# Main.net
KiCad netlist of a schematic drawn in Altium Designer
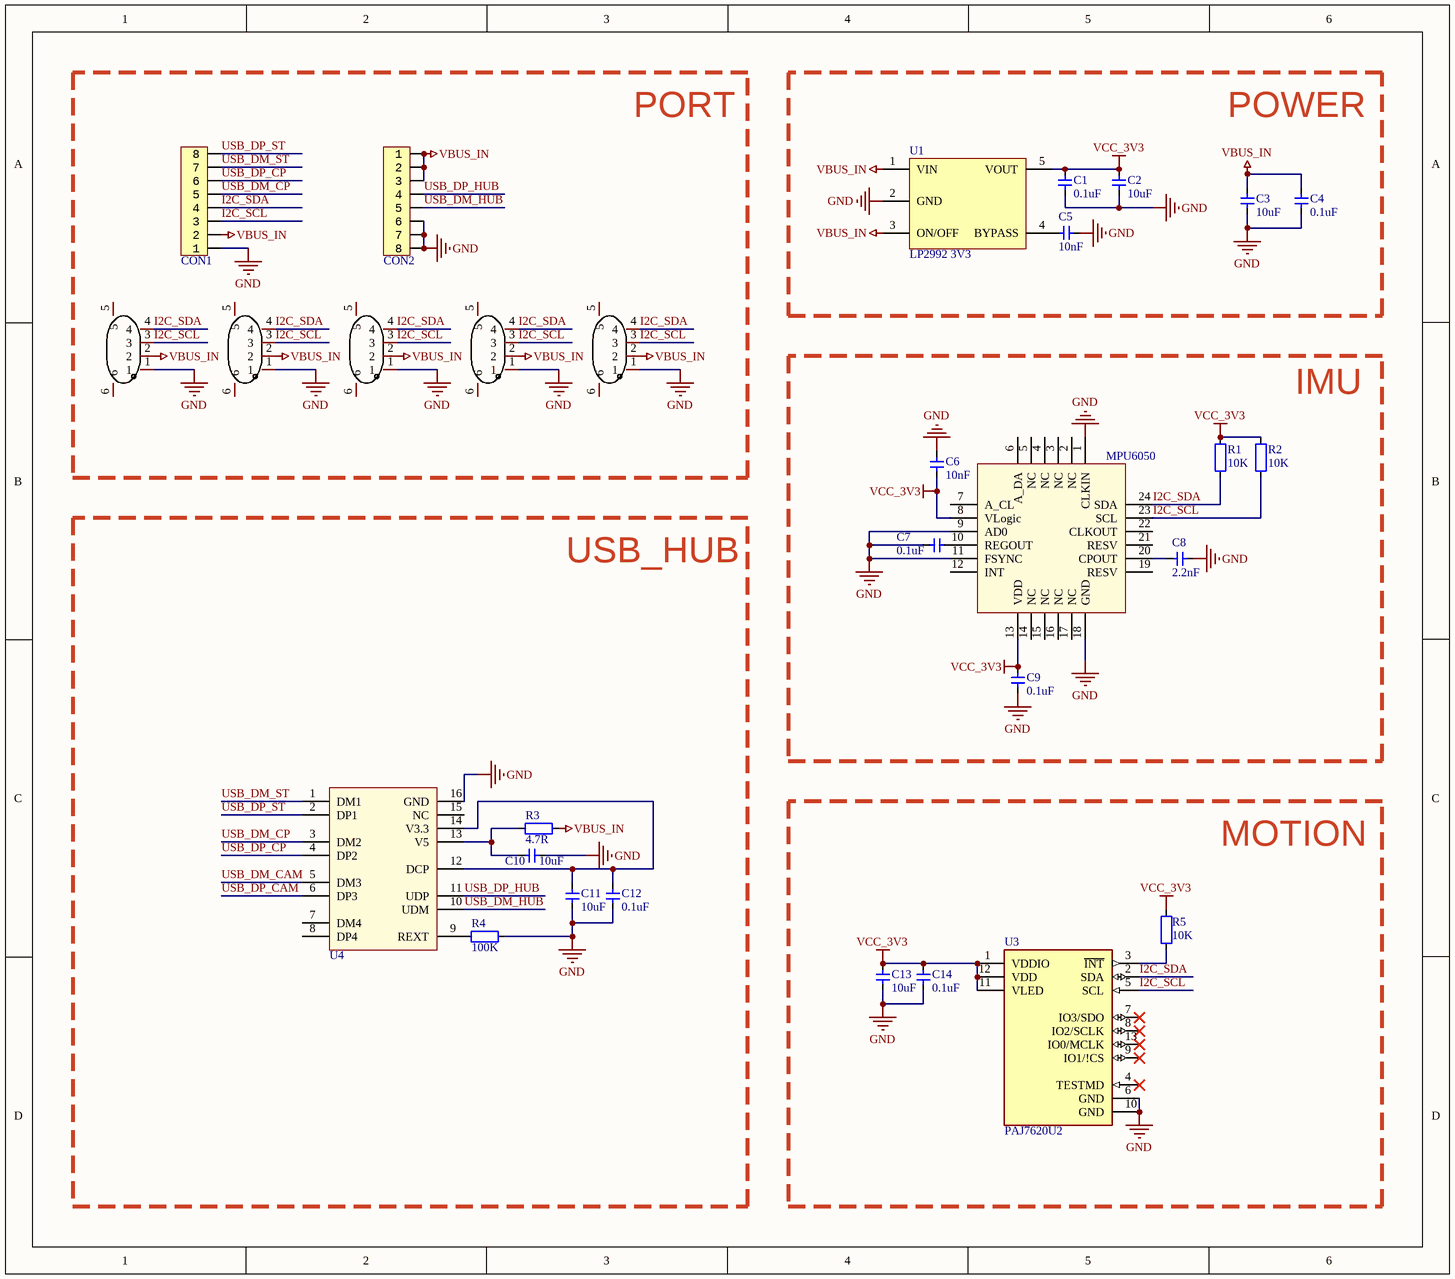
[diagram p0: Main.SchDoc]

(export (version "E")
  (design (tool "Eeschema 10.0.6"))
  (components
    (comp (ref "C1")
      (value "0.1uF")
      (footprint "CAP_0402")
      (description "Capacitor")
      (libsource (lib "MyPcbLib") (part "电容-0402"))
    )
    (comp (ref "C2")
      (value "10uF")
      (footprint "CAP_0402")
      (description "Capacitor")
      (libsource (lib "MyPcbLib") (part "电容-0402"))
    )
    (comp (ref "C3")
      (value "10uF")
      (footprint "CAP_0402")
      (description "Capacitor")
      (libsource (lib "MyPcbLib") (part "电容-0402"))
    )
    (comp (ref "C4")
      (value "0.1uF")
      (footprint "CAP_0402")
      (description "Capacitor")
      (libsource (lib "MyPcbLib") (part "电容-0402"))
    )
    (comp (ref "C5")
      (value "10nF")
      (footprint "CAP_0402")
      (description "Capacitor")
      (libsource (lib "MyPcbLib") (part "电容-0402"))
    )
    (comp (ref "C6")
      (value "10nF")
      (footprint "CAP_0402")
      (description "Capacitor")
      (libsource (lib "MyPcbLib") (part "电容-0402"))
    )
    (comp (ref "C7")
      (value "0.1uF")
      (footprint "CAP_0402")
      (description "Capacitor")
      (libsource (lib "MyPcbLib") (part "电容-0402"))
    )
    (comp (ref "C8")
      (value "2.2nF")
      (footprint "CAP_0402")
      (description "Capacitor")
      (libsource (lib "MyPcbLib") (part "电容-0402"))
    )
    (comp (ref "C9")
      (value "0.1uF")
      (footprint "CAP_0402")
      (description "Capacitor")
      (libsource (lib "MyPcbLib") (part "电容-0402"))
    )
    (comp (ref "C10")
      (value "10uF")
      (footprint "CAP_0402")
      (description "Capacitor")
      (libsource (lib "MyPcbLib") (part "电容-0402"))
    )
    (comp (ref "C11")
      (value "10uF")
      (footprint "CAP_0402")
      (description "Capacitor")
      (libsource (lib "MyPcbLib") (part "电容-0402"))
    )
    (comp (ref "C12")
      (value "0.1uF")
      (footprint "CAP_0402")
      (description "Capacitor")
      (libsource (lib "MyPcbLib") (part "电容-0402"))
    )
    (comp (ref "C13")
      (value "10uF")
      (footprint "CAP_0402")
      (description "Capacitor")
      (libsource (lib "MyPcbLib") (part "电容-0402"))
    )
    (comp (ref "C14")
      (value "0.1uF")
      (footprint "CAP_0402")
      (description "Capacitor")
      (libsource (lib "MyPcbLib") (part "电容-0402"))
    )
    (comp (ref "CON1")
      (value "FFC_0.5_8")
      (footprint "FFC_0.5_8")
      (description "FFC")
      (libsource (lib "") (part "FFC_0.5_8_1"))
    )
    (comp (ref "CON2")
      (value "FFC_0.5_8")
      (footprint "FFC_0.5_8")
      (description "FFC")
      (libsource (lib "KitSprout") (part "FFC_0.5_8"))
    )
    (comp (ref "FPC1")
      (value "0.5K-DX-4PWB")
      (footprint "FPC-SMD_4P-P0.50_DEALON_0.5K-DX-4PWB")
      (fields (field (name "MANUFACTURER") "HDGC(华德共创)"))
      (libsource (lib "altium-import") (part "root_2_0.5K-DX-4PWB_"))
    )
    (comp (ref "FPC2")
      (value "0.5K-DX-4PWB")
      (footprint "FPC-SMD_4P-P0.50_DEALON_0.5K-DX-4PWB")
      (fields (field (name "MANUFACTURER") "HDGC(华德共创)"))
      (libsource (lib "altium-import") (part "root_2_0.5K-DX-4PWB_"))
    )
    (comp (ref "FPC3")
      (value "0.5K-DX-4PWB")
      (footprint "FPC-SMD_4P-P0.50_DEALON_0.5K-DX-4PWB")
      (fields (field (name "MANUFACTURER") "HDGC(华德共创)"))
      (libsource (lib "altium-import") (part "root_2_0.5K-DX-4PWB_"))
    )
    (comp (ref "FPC4")
      (value "0.5K-DX-4PWB")
      (footprint "FPC-SMD_4P-P0.50_DEALON_0.5K-DX-4PWB")
      (fields (field (name "MANUFACTURER") "HDGC(华德共创)"))
      (libsource (lib "altium-import") (part "root_2_0.5K-DX-4PWB_"))
    )
    (comp (ref "FPC5")
      (value "0.5K-DX-4PWB")
      (footprint "FPC-SMD_4P-P0.50_DEALON_0.5K-DX-4PWB")
      (fields (field (name "MANUFACTURER") "HDGC(华德共创)"))
      (libsource (lib "altium-import") (part "root_2_0.5K-DX-4PWB_"))
    )
    (comp (ref "R1")
      (value "10K")
      (footprint "RES_0402")
      (description "Resistor")
      (libsource (lib "") (part "电阻-0402_2"))
    )
    (comp (ref "R2")
      (value "10K")
      (footprint "RES_0402")
      (description "Resistor")
      (libsource (lib "") (part "电阻-0402_2"))
    )
    (comp (ref "R3")
      (value "4.7R")
      (footprint "RES_0402")
      (description "Resistor")
      (libsource (lib "") (part "电阻-0402_1"))
    )
    (comp (ref "R4")
      (value "100K")
      (footprint "RES_0402")
      (description "Resistor")
      (libsource (lib "") (part "电阻-0402_1"))
    )
    (comp (ref "R5")
      (value "10K")
      (footprint "RES_0402")
      (description "Resistor")
      (libsource (lib "MyPcbLib") (part "电阻-0402"))
    )
    (comp (ref "U1")
      (value "LP2992 3V3")
      (footprint "SOT23-5")
      (description "LDO")
      (libsource (lib "MyPcbLib") (part "LP2992"))
    )
    (comp (ref "U2")
      (value "MPU6050")
      (footprint "QFN-24")
      (description "六轴传感器")
      (libsource (lib "mLib") (part "MPU6050"))
    )
    (comp (ref "U3")
      (value "PAJ7620U2")
      (footprint "PAJ7620U2")
      (description "module sensorPAJ7620U2 : 54/TRAY, 5400/BOX, 32400/CARTON")
      (fields (field (name "MF") "Pixart"))
      (libsource (lib "MyPcbLib") (part "PAJ7620U2"))
    )
    (comp (ref "U4")
      (value "HS8836A")
      (footprint "SO-16N")
      (description "USB2.0 HUB")
      (libsource (lib "MyPcbLib") (part "HS8836A"))
    )
  )
  (nets
    (net (code "1") (name "/I2C_SCL") (class "Default")
      (node (ref "CON1") (pin "3") (pinfunction "3_3") (pintype "passive"))
      (node (ref "FPC1") (pin "3") (pinfunction "3_3") (pintype "passive"))
      (node (ref "FPC2") (pin "3") (pinfunction "3_3") (pintype "passive"))
      (node (ref "FPC3") (pin "3") (pinfunction "3_3") (pintype "passive"))
      (node (ref "FPC4") (pin "3") (pinfunction "3_3") (pintype "passive"))
      (node (ref "FPC5") (pin "3") (pinfunction "3_3") (pintype "passive"))
      (node (ref "R2") (pin "1") (pinfunction "1_1") (pintype "passive"))
      (node (ref "U2") (pin "23") (pinfunction "SCL_23") (pintype "passive"))
      (node (ref "U3") (pin "5") (pinfunction "SCL_5") (pintype "input"))
    )
    (net (code "2") (name "/I2C_SDA") (class "Default")
      (node (ref "CON1") (pin "4") (pinfunction "4_4") (pintype "passive"))
      (node (ref "FPC1") (pin "4") (pinfunction "4_4") (pintype "passive"))
      (node (ref "FPC2") (pin "4") (pinfunction "4_4") (pintype "passive"))
      (node (ref "FPC3") (pin "4") (pinfunction "4_4") (pintype "passive"))
      (node (ref "FPC4") (pin "4") (pinfunction "4_4") (pintype "passive"))
      (node (ref "FPC5") (pin "4") (pinfunction "4_4") (pintype "passive"))
      (node (ref "R1") (pin "1") (pinfunction "1_1") (pintype "passive"))
      (node (ref "U2") (pin "24") (pinfunction "SDA_24") (pintype "passive"))
      (node (ref "U3") (pin "2") (pinfunction "SDA_2") (pintype "bidirectional"))
    )
    (net (code "3") (name "/USB_DM_CAM") (class "Default")
      (node (ref "U4") (pin "5") (pinfunction "DM3_5") (pintype "passive"))
    )
    (net (code "4") (name "/USB_DM_CP") (class "Default")
      (node (ref "CON1") (pin "5") (pinfunction "5_5") (pintype "passive"))
      (node (ref "U4") (pin "3") (pinfunction "DM2_3") (pintype "passive"))
    )
    (net (code "5") (name "/USB_DM_HUB") (class "Default")
      (node (ref "CON2") (pin "5") (pinfunction "5_5") (pintype "passive"))
      (node (ref "U4") (pin "10") (pinfunction "UDM_10") (pintype "passive"))
    )
    (net (code "6") (name "/USB_DM_ST") (class "Default")
      (node (ref "CON1") (pin "7") (pinfunction "7_7") (pintype "passive"))
      (node (ref "U4") (pin "1") (pinfunction "DM1_1") (pintype "passive"))
    )
    (net (code "7") (name "/USB_DP_CAM") (class "Default")
      (node (ref "U4") (pin "6") (pinfunction "DP3_6") (pintype "passive"))
    )
    (net (code "8") (name "/USB_DP_CP") (class "Default")
      (node (ref "CON1") (pin "6") (pinfunction "6_6") (pintype "passive"))
      (node (ref "U4") (pin "4") (pinfunction "DP2_4") (pintype "passive"))
    )
    (net (code "9") (name "/USB_DP_HUB") (class "Default")
      (node (ref "CON2") (pin "4") (pinfunction "4_4") (pintype "passive"))
      (node (ref "U4") (pin "11") (pinfunction "UDP_11") (pintype "passive"))
    )
    (net (code "10") (name "/USB_DP_ST") (class "Default")
      (node (ref "CON1") (pin "8") (pinfunction "8_8") (pintype "passive"))
      (node (ref "U4") (pin "2") (pinfunction "DP1_2") (pintype "passive"))
    )
    (net (code "11") (name "GND") (class "Default")
      (node (ref "C1") (pin "1") (pinfunction "1_1") (pintype "passive"))
      (node (ref "C10") (pin "1") (pinfunction "1_1") (pintype "passive"))
      (node (ref "C11") (pin "2") (pinfunction "2_2") (pintype "passive"))
      (node (ref "C12") (pin "2") (pinfunction "2_2") (pintype "passive"))
      (node (ref "C13") (pin "2") (pinfunction "2_2") (pintype "passive"))
      (node (ref "C14") (pin "2") (pinfunction "2_2") (pintype "passive"))
      (node (ref "C2") (pin "1") (pinfunction "1_1") (pintype "passive"))
      (node (ref "C3") (pin "1") (pinfunction "1_1") (pintype "passive"))
      (node (ref "C4") (pin "1") (pinfunction "1_1") (pintype "passive"))
      (node (ref "C5") (pin "1") (pinfunction "1_1") (pintype "passive"))
      (node (ref "C6") (pin "2") (pinfunction "2_2") (pintype "passive"))
      (node (ref "C7") (pin "2") (pinfunction "2_2") (pintype "passive"))
      (node (ref "C8") (pin "1") (pinfunction "1_1") (pintype "passive"))
      (node (ref "C9") (pin "1") (pinfunction "1_1") (pintype "passive"))
      (node (ref "CON1") (pin "1") (pinfunction "1_1") (pintype "passive"))
      (node (ref "CON2") (pin "6") (pinfunction "6_6") (pintype "passive"))
      (node (ref "CON2") (pin "7") (pinfunction "7_7") (pintype "passive"))
      (node (ref "CON2") (pin "8") (pinfunction "8_8") (pintype "passive"))
      (node (ref "FPC1") (pin "1") (pinfunction "1_1") (pintype "passive"))
      (node (ref "FPC2") (pin "1") (pinfunction "1_1") (pintype "passive"))
      (node (ref "FPC3") (pin "1") (pinfunction "1_1") (pintype "passive"))
      (node (ref "FPC4") (pin "1") (pinfunction "1_1") (pintype "passive"))
      (node (ref "FPC5") (pin "1") (pinfunction "1_1") (pintype "passive"))
      (node (ref "R4") (pin "1") (pinfunction "1_1") (pintype "passive"))
      (node (ref "U1") (pin "2") (pinfunction "GND_2") (pintype "passive"))
      (node (ref "U2") (pin "1") (pinfunction "CLKIN_1") (pintype "passive"))
      (node (ref "U2") (pin "11") (pinfunction "FSYNC_11") (pintype "passive"))
      (node (ref "U2") (pin "18") (pinfunction "GND_18") (pintype "passive"))
      (node (ref "U2") (pin "9") (pinfunction "AD0_9") (pintype "passive"))
      (node (ref "U3") (pin "10") (pinfunction "GND_10") (pintype "passive"))
      (node (ref "U3") (pin "6") (pinfunction "GND_6") (pintype "passive"))
      (node (ref "U4") (pin "16") (pinfunction "GND_16") (pintype "passive"))
    )
    (net (code "12") (name "Net-(U1-BYPASS)") (class "Default")
      (node (ref "C5") (pin "2") (pinfunction "2_2") (pintype "passive"))
      (node (ref "U1") (pin "4") (pinfunction "BYPASS_4") (pintype "passive"))
    )
    (net (code "13") (name "Net-(U2-CPOUT)") (class "Default")
      (node (ref "C8") (pin "2") (pinfunction "2_2") (pintype "passive"))
      (node (ref "U2") (pin "20") (pinfunction "CPOUT_20") (pintype "passive"))
    )
    (net (code "14") (name "Net-(U2-REGOUT)") (class "Default")
      (node (ref "C7") (pin "1") (pinfunction "1_1") (pintype "passive"))
      (node (ref "U2") (pin "10") (pinfunction "REGOUT_10") (pintype "passive"))
    )
    (net (code "15") (name "Net-(U3-~{INT})") (class "Default")
      (node (ref "R5") (pin "2") (pinfunction "2_2") (pintype "passive"))
      (node (ref "U3") (pin "3") (pinfunction "~{INT}_3") (pintype "output"))
    )
    (net (code "16") (name "Net-(U4-DCP)") (class "Default")
      (node (ref "C11") (pin "1") (pinfunction "1_1") (pintype "passive"))
      (node (ref "C12") (pin "1") (pinfunction "1_1") (pintype "passive"))
      (node (ref "U4") (pin "12") (pinfunction "DCP_12") (pintype "passive"))
      (node (ref "U4") (pin "14") (pinfunction "V3.3_14") (pintype "passive"))
    )
    (net (code "17") (name "Net-(U4-REXT)") (class "Default")
      (node (ref "R4") (pin "2") (pinfunction "2_2") (pintype "passive"))
      (node (ref "U4") (pin "9") (pinfunction "REXT_9") (pintype "passive"))
    )
    (net (code "18") (name "Net-(U4-V5)") (class "Default")
      (node (ref "C10") (pin "2") (pinfunction "2_2") (pintype "passive"))
      (node (ref "R3") (pin "2") (pinfunction "2_2") (pintype "passive"))
      (node (ref "U4") (pin "13") (pinfunction "V5_13") (pintype "passive"))
    )
    (net (code "19") (name "VBUS_IN") (class "Default")
      (node (ref "C3") (pin "2") (pinfunction "2_2") (pintype "passive"))
      (node (ref "C4") (pin "2") (pinfunction "2_2") (pintype "passive"))
      (node (ref "CON1") (pin "2") (pinfunction "2_2") (pintype "passive"))
      (node (ref "CON2") (pin "1") (pinfunction "1_1") (pintype "passive"))
      (node (ref "CON2") (pin "2") (pinfunction "2_2") (pintype "passive"))
      (node (ref "CON2") (pin "3") (pinfunction "3_3") (pintype "passive"))
      (node (ref "FPC1") (pin "2") (pinfunction "2_2") (pintype "passive"))
      (node (ref "FPC2") (pin "2") (pinfunction "2_2") (pintype "passive"))
      (node (ref "FPC3") (pin "2") (pinfunction "2_2") (pintype "passive"))
      (node (ref "FPC4") (pin "2") (pinfunction "2_2") (pintype "passive"))
      (node (ref "FPC5") (pin "2") (pinfunction "2_2") (pintype "passive"))
      (node (ref "R3") (pin "1") (pinfunction "1_1") (pintype "passive"))
      (node (ref "U1") (pin "1") (pinfunction "VIN_1") (pintype "passive"))
      (node (ref "U1") (pin "3") (pinfunction "ON/OFF_3") (pintype "passive"))
    )
    (net (code "20") (name "VCC_3V3") (class "Default")
      (node (ref "C1") (pin "2") (pinfunction "2_2") (pintype "passive"))
      (node (ref "C13") (pin "1") (pinfunction "1_1") (pintype "passive"))
      (node (ref "C14") (pin "1") (pinfunction "1_1") (pintype "passive"))
      (node (ref "C2") (pin "2") (pinfunction "2_2") (pintype "passive"))
      (node (ref "C6") (pin "1") (pinfunction "1_1") (pintype "passive"))
      (node (ref "C9") (pin "2") (pinfunction "2_2") (pintype "passive"))
      (node (ref "R1") (pin "2") (pinfunction "2_2") (pintype "passive"))
      (node (ref "R2") (pin "2") (pinfunction "2_2") (pintype "passive"))
      (node (ref "R5") (pin "1") (pinfunction "1_1") (pintype "passive"))
      (node (ref "U1") (pin "5") (pinfunction "VOUT_5") (pintype "passive"))
      (node (ref "U2") (pin "13") (pinfunction "VDD_13") (pintype "passive"))
      (node (ref "U2") (pin "8") (pinfunction "VLogic_8") (pintype "passive"))
      (node (ref "U3") (pin "1") (pinfunction "VDDIO_1") (pintype "power_in"))
      (node (ref "U3") (pin "11") (pinfunction "VLED_11") (pintype "power_in"))
      (node (ref "U3") (pin "12") (pinfunction "VDD_12") (pintype "power_in"))
    )
    (net (code "21") (name "unconnected-(FPC1-Pad5)") (class "Default")
      (node (ref "FPC1") (pin "5") (pinfunction "5_5") (pintype "passive"))
    )
    (net (code "22") (name "unconnected-(FPC1-Pad6)") (class "Default")
      (node (ref "FPC1") (pin "6") (pinfunction "6_6") (pintype "passive"))
    )
    (net (code "23") (name "unconnected-(FPC2-Pad5)") (class "Default")
      (node (ref "FPC2") (pin "5") (pinfunction "5_5") (pintype "passive"))
    )
    (net (code "24") (name "unconnected-(FPC2-Pad6)") (class "Default")
      (node (ref "FPC2") (pin "6") (pinfunction "6_6") (pintype "passive"))
    )
    (net (code "25") (name "unconnected-(FPC3-Pad5)") (class "Default")
      (node (ref "FPC3") (pin "5") (pinfunction "5_5") (pintype "passive"))
    )
    (net (code "26") (name "unconnected-(FPC3-Pad6)") (class "Default")
      (node (ref "FPC3") (pin "6") (pinfunction "6_6") (pintype "passive"))
    )
    (net (code "27") (name "unconnected-(FPC4-Pad5)") (class "Default")
      (node (ref "FPC4") (pin "5") (pinfunction "5_5") (pintype "passive"))
    )
    (net (code "28") (name "unconnected-(FPC4-Pad6)") (class "Default")
      (node (ref "FPC4") (pin "6") (pinfunction "6_6") (pintype "passive"))
    )
    (net (code "29") (name "unconnected-(FPC5-Pad5)") (class "Default")
      (node (ref "FPC5") (pin "5") (pinfunction "5_5") (pintype "passive"))
    )
    (net (code "30") (name "unconnected-(FPC5-Pad6)") (class "Default")
      (node (ref "FPC5") (pin "6") (pinfunction "6_6") (pintype "passive"))
    )
    (net (code "31") (name "unconnected-(U2-A_CL-Pad7)") (class "Default")
      (node (ref "U2") (pin "7") (pinfunction "A_CL_7") (pintype "passive"))
    )
    (net (code "32") (name "unconnected-(U2-A_DA-Pad6)") (class "Default")
      (node (ref "U2") (pin "6") (pinfunction "A_DA_6") (pintype "passive"))
    )
    (net (code "33") (name "unconnected-(U2-CLKOUT-Pad22)") (class "Default")
      (node (ref "U2") (pin "22") (pinfunction "CLKOUT_22") (pintype "passive"))
    )
    (net (code "34") (name "unconnected-(U2-INT-Pad12)") (class "Default")
      (node (ref "U2") (pin "12") (pinfunction "INT_12") (pintype "passive"))
    )
    (net (code "35") (name "unconnected-(U2-NC-Pad2)") (class "Default")
      (node (ref "U2") (pin "2") (pinfunction "NC_2") (pintype "passive"))
    )
    (net (code "36") (name "unconnected-(U2-NC-Pad3)") (class "Default")
      (node (ref "U2") (pin "3") (pinfunction "NC_3") (pintype "passive"))
    )
    (net (code "37") (name "unconnected-(U2-NC-Pad4)") (class "Default")
      (node (ref "U2") (pin "4") (pinfunction "NC_4") (pintype "passive"))
    )
    (net (code "38") (name "unconnected-(U2-NC-Pad5)") (class "Default")
      (node (ref "U2") (pin "5") (pinfunction "NC_5") (pintype "passive"))
    )
    (net (code "39") (name "unconnected-(U2-NC-Pad14)") (class "Default")
      (node (ref "U2") (pin "14") (pinfunction "NC_14") (pintype "passive"))
    )
    (net (code "40") (name "unconnected-(U2-NC-Pad15)") (class "Default")
      (node (ref "U2") (pin "15") (pinfunction "NC_15") (pintype "passive"))
    )
    (net (code "41") (name "unconnected-(U2-NC-Pad16)") (class "Default")
      (node (ref "U2") (pin "16") (pinfunction "NC_16") (pintype "passive"))
    )
    (net (code "42") (name "unconnected-(U2-NC-Pad17)") (class "Default")
      (node (ref "U2") (pin "17") (pinfunction "NC_17") (pintype "passive"))
    )
    (net (code "43") (name "unconnected-(U2-RESV-Pad19)") (class "Default")
      (node (ref "U2") (pin "19") (pinfunction "RESV_19") (pintype "passive"))
    )
    (net (code "44") (name "unconnected-(U2-RESV-Pad21)") (class "Default")
      (node (ref "U2") (pin "21") (pinfunction "RESV_21") (pintype "passive"))
    )
    (net (code "45") (name "unconnected-(U3-IO0{slash}MCLK-Pad13)") (class "Default")
      (node (ref "U3") (pin "13") (pinfunction "IO0/MCLK_13") (pintype "bidirectional+no_connect"))
    )
    (net (code "46") (name "unconnected-(U3-IO1{slash}!CS-Pad9)") (class "Default")
      (node (ref "U3") (pin "9") (pinfunction "IO1/!CS_9") (pintype "bidirectional+no_connect"))
    )
    (net (code "47") (name "unconnected-(U3-IO2{slash}SCLK-Pad8)") (class "Default")
      (node (ref "U3") (pin "8") (pinfunction "IO2/SCLK_8") (pintype "bidirectional+no_connect"))
    )
    (net (code "48") (name "unconnected-(U3-IO3{slash}SDO-Pad7)") (class "Default")
      (node (ref "U3") (pin "7") (pinfunction "IO3/SDO_7") (pintype "bidirectional+no_connect"))
    )
    (net (code "49") (name "unconnected-(U3-TESTMD-Pad4)") (class "Default")
      (node (ref "U3") (pin "4") (pinfunction "TESTMD_4") (pintype "input+no_connect"))
    )
    (net (code "50") (name "unconnected-(U4-DM4-Pad7)") (class "Default")
      (node (ref "U4") (pin "7") (pinfunction "DM4_7") (pintype "passive"))
    )
    (net (code "51") (name "unconnected-(U4-DP4-Pad8)") (class "Default")
      (node (ref "U4") (pin "8") (pinfunction "DP4_8") (pintype "passive"))
    )
    (net (code "52") (name "unconnected-(U4-NC-Pad15)") (class "Default")
      (node (ref "U4") (pin "15") (pinfunction "NC_15") (pintype "passive"))
    )
  )
)
